# 1_Power.net
KiCad netlist of a schematic drawn in Altium Designer
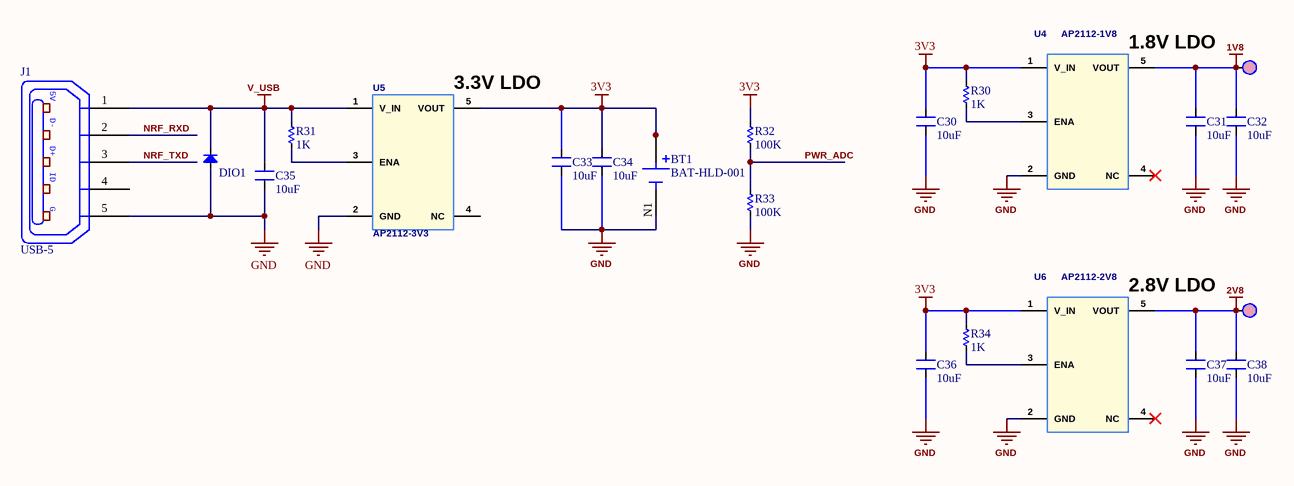
[diagram p0: [1]Power.SchDoc]

(export (version "E")
  (design (tool "Eeschema 10.0.6"))
  (components
    (comp (ref "BT1")
      (value "BAT-HLD-001")
      (footprint "BAT_BAT-HLD-001:BAT_BAT-HLD-001")
      (description "Holder for CR2032 and CR2025 Batteries, Surface-Mount, Bulk Packaging")
      (fields (field (name "MF") "Linx Technologies"))
      (libsource (lib "BAT-HLD-001") (part "BAT-HLD-001"))
    )
    (comp (ref "C30")
      (value "10uF")
      (footprint "CN-SMD-0603")
      (description "Tu gom")
      (libsource (lib "LIBTanCN") (part "CN"))
    )
    (comp (ref "C31")
      (value "10uF")
      (footprint "CN-SMD-0603")
      (description "Tu gom")
      (libsource (lib "LIBTanCN") (part "CN"))
    )
    (comp (ref "C32")
      (value "10uF")
      (footprint "CN-SMD-0603")
      (description "Tu gom")
      (libsource (lib "LIBTanCN") (part "CN"))
    )
    (comp (ref "C33")
      (value "10uF")
      (footprint "CN-SMD-0603")
      (description "Tu gom")
      (libsource (lib "LIBTanCN") (part "CN"))
    )
    (comp (ref "C34")
      (value "10uF")
      (footprint "CN-SMD-0603")
      (description "Tu gom")
      (libsource (lib "LIBTanCN") (part "CN"))
    )
    (comp (ref "C35")
      (value "10uF")
      (footprint "CN-SMD-0603")
      (description "Tu gom")
      (libsource (lib "LIBTanCN") (part "CN"))
    )
    (comp (ref "C36")
      (value "10uF")
      (footprint "CN-SMD-0603")
      (description "Tu gom")
      (libsource (lib "LIBTanCN") (part "CN"))
    )
    (comp (ref "C37")
      (value "10uF")
      (footprint "CN-SMD-0603")
      (description "Tu gom")
      (libsource (lib "LIBTanCN") (part "CN"))
    )
    (comp (ref "C38")
      (value "10uF")
      (footprint "CN-SMD-0603")
      (description "Tu gom")
      (libsource (lib "LIBTanCN") (part "CN"))
    )
    (comp (ref "DIO1")
      (value "Diode SMD")
      (footprint "DIO-SMD-123")
      (description "Default Diode")
      (fields (field (name "PUBLISHER") "Altium Limited"))
      (libsource (lib "LIBRARY") (part "Diode SMD"))
    )
    (comp (ref "J1")
      (value "USB-5")
      (footprint "USB-M1")
      (fields
        (field (name "MANUFACTURER") "FCI")
        (field (name "MANUFACTURER PART NUMBER") "10118193-0001LF")
        (field (name ".CREATOR") "MM")
        (field (name ".CHECKED PCB") "RF")
        (field (name ".CHECKED SCH") "MM")
      )
      (libsource (lib "LIBRARY") (part "USB-5"))
    )
    (comp (ref "R30")
      (value "1K")
      (footprint "RES-SMD-0603")
      (description "Resistor")
      (fields
        (field (name "MANUFACTURER") "Generic Components")
        (field (name "PUBLISHER") "Altium Hobart Technology Centre")
      )
      (libsource (lib "LIBRARY") (part "Res-SMD"))
    )
    (comp (ref "R31")
      (value "1K")
      (footprint "RES-SMD-0603")
      (description "Resistor")
      (fields
        (field (name "MANUFACTURER") "Generic Components")
        (field (name "PUBLISHER") "Altium Hobart Technology Centre")
      )
      (libsource (lib "LIBRARY") (part "Res-SMD"))
    )
    (comp (ref "R32")
      (value "100K")
      (footprint "RES-SMD-0603")
      (description "Resistor")
      (fields
        (field (name "MANUFACTURER") "Generic Components")
        (field (name "PUBLISHER") "Altium Hobart Technology Centre")
      )
      (libsource (lib "LIBRARY") (part "Res-SMD"))
    )
    (comp (ref "R33")
      (value "100K")
      (footprint "RES-SMD-0603")
      (description "Resistor")
      (fields
        (field (name "MANUFACTURER") "Generic Components")
        (field (name "PUBLISHER") "Altium Hobart Technology Centre")
      )
      (libsource (lib "LIBRARY") (part "Res-SMD"))
    )
    (comp (ref "R34")
      (value "1K")
      (footprint "RES-SMD-0603")
      (description "Resistor")
      (fields
        (field (name "MANUFACTURER") "Generic Components")
        (field (name "PUBLISHER") "Altium Hobart Technology Centre")
      )
      (libsource (lib "LIBRARY") (part "Res-SMD"))
    )
    (comp (ref "TP6")
      (value "TP")
      (footprint "P-TP 1MM")
      (libsource (lib "VitalSignal EcgPpg Board") (part "P-TESTPOINT"))
    )
    (comp (ref "TP7")
      (value "TP")
      (footprint "P-TP 1MM")
      (libsource (lib "VitalSignal EcgPpg Board") (part "P-TESTPOINT"))
    )
    (comp (ref "U4")
      (value "AP2112-1V8")
      (footprint "SOT235_AP2112")
      (description "600mA CMOS LDO REGULATOR WITH ENABLE")
      (libsource (lib "VitalSignal EcgPpg Board") (part "AP2112-1V8"))
    )
    (comp (ref "U5")
      (value "AP2112-3V3")
      (footprint "SOT235_AP2112")
      (description "600mA CMOS LDO REGULATOR WITH ENABLE")
      (libsource (lib "VitalSignal EcgPpg Board") (part "AP2112-3V3"))
    )
    (comp (ref "U6")
      (value "AP2112-2V8")
      (footprint "SOT235_AP2112")
      (description "600mA CMOS LDO REGULATOR WITH ENABLE")
      (libsource (lib "VitalSignal EcgPpg Board") (part "AP2112-1V8"))
    )
  )
  (nets
    (net (code "1") (name "/NRF_RXD") (class "Default")
      (node (ref "J1") (pin "2") (pinfunction "P2_2") (pintype "passive"))
    )
    (net (code "2") (name "/NRF_TXD") (class "Default")
      (node (ref "J1") (pin "3") (pinfunction "P3_3") (pintype "passive"))
    )
    (net (code "3") (name "/PWR_ADC") (class "Default")
      (node (ref "R32") (pin "2") (pinfunction "2_2") (pintype "passive"))
      (node (ref "R33") (pin "1") (pinfunction "1_1") (pintype "passive"))
    )
    (net (code "4") (name "1V8") (class "Default")
      (node (ref "C31") (pin "2") (pinfunction "2_2") (pintype "passive"))
      (node (ref "C32") (pin "2") (pinfunction "2_2") (pintype "passive"))
      (node (ref "TP6") (pin "1") (pinfunction "1_1") (pintype "passive"))
      (node (ref "U4") (pin "5") (pinfunction "VOUT_5") (pintype "passive"))
    )
    (net (code "5") (name "2V8") (class "Default")
      (node (ref "C37") (pin "2") (pinfunction "2_2") (pintype "passive"))
      (node (ref "C38") (pin "2") (pinfunction "2_2") (pintype "passive"))
      (node (ref "TP7") (pin "1") (pinfunction "1_1") (pintype "passive"))
      (node (ref "U6") (pin "5") (pinfunction "VOUT_5") (pintype "passive"))
    )
    (net (code "6") (name "3V3") (class "Default")
      (node (ref "BT1") (pin "P1") (pinfunction "POS_P1") (pintype "passive"))
      (node (ref "BT1") (pin "P2") (pinfunction "POS_P2") (pintype "passive"))
      (node (ref "C30") (pin "2") (pinfunction "2_2") (pintype "passive"))
      (node (ref "C33") (pin "2") (pinfunction "2_2") (pintype "passive"))
      (node (ref "C34") (pin "2") (pinfunction "2_2") (pintype "passive"))
      (node (ref "C36") (pin "2") (pinfunction "2_2") (pintype "passive"))
      (node (ref "R30") (pin "1") (pinfunction "1_1") (pintype "passive"))
      (node (ref "R32") (pin "1") (pinfunction "1_1") (pintype "passive"))
      (node (ref "R34") (pin "1") (pinfunction "1_1") (pintype "passive"))
      (node (ref "U4") (pin "1") (pinfunction "V_IN_1") (pintype "passive"))
      (node (ref "U5") (pin "5") (pinfunction "VOUT_5") (pintype "passive"))
      (node (ref "U6") (pin "1") (pinfunction "V_IN_1") (pintype "passive"))
    )
    (net (code "7") (name "GND") (class "Default")
      (node (ref "BT1") (pin "N1") (pinfunction "NEG_N1") (pintype "passive"))
      (node (ref "C30") (pin "1") (pinfunction "1_1") (pintype "passive"))
      (node (ref "C31") (pin "1") (pinfunction "1_1") (pintype "passive"))
      (node (ref "C32") (pin "1") (pinfunction "1_1") (pintype "passive"))
      (node (ref "C33") (pin "1") (pinfunction "1_1") (pintype "passive"))
      (node (ref "C34") (pin "1") (pinfunction "1_1") (pintype "passive"))
      (node (ref "C35") (pin "1") (pinfunction "1_1") (pintype "passive"))
      (node (ref "C36") (pin "1") (pinfunction "1_1") (pintype "passive"))
      (node (ref "C37") (pin "1") (pinfunction "1_1") (pintype "passive"))
      (node (ref "C38") (pin "1") (pinfunction "1_1") (pintype "passive"))
      (node (ref "DIO1") (pin "1") (pinfunction "A_1") (pintype "passive"))
      (node (ref "J1") (pin "5") (pinfunction "P5_5") (pintype "passive"))
      (node (ref "R33") (pin "2") (pinfunction "2_2") (pintype "passive"))
      (node (ref "U4") (pin "2") (pinfunction "GND_2") (pintype "passive"))
      (node (ref "U5") (pin "2") (pinfunction "GND_2") (pintype "passive"))
      (node (ref "U6") (pin "2") (pinfunction "GND_2") (pintype "passive"))
    )
    (net (code "8") (name "Net-(U4-ENA)") (class "Default")
      (node (ref "R30") (pin "2") (pinfunction "2_2") (pintype "passive"))
      (node (ref "U4") (pin "3") (pinfunction "ENA_3") (pintype "passive"))
    )
    (net (code "9") (name "Net-(U5-ENA)") (class "Default")
      (node (ref "R31") (pin "2") (pinfunction "2_2") (pintype "passive"))
      (node (ref "U5") (pin "3") (pinfunction "ENA_3") (pintype "passive"))
    )
    (net (code "10") (name "Net-(U6-ENA)") (class "Default")
      (node (ref "R34") (pin "2") (pinfunction "2_2") (pintype "passive"))
      (node (ref "U6") (pin "3") (pinfunction "ENA_3") (pintype "passive"))
    )
    (net (code "11") (name "V_USB") (class "Default")
      (node (ref "C35") (pin "2") (pinfunction "2_2") (pintype "passive"))
      (node (ref "DIO1") (pin "2") (pinfunction "K_2") (pintype "passive"))
      (node (ref "J1") (pin "1") (pinfunction "P1_1") (pintype "passive"))
      (node (ref "R31") (pin "1") (pinfunction "1_1") (pintype "passive"))
      (node (ref "U5") (pin "1") (pinfunction "V_IN_1") (pintype "passive"))
    )
    (net (code "12") (name "unconnected-(J1-P4-Pad4)") (class "Default")
      (node (ref "J1") (pin "4") (pinfunction "P4_4") (pintype "passive"))
    )
    (net (code "13") (name "unconnected-(U4-NC-Pad4)") (class "Default")
      (node (ref "U4") (pin "4") (pinfunction "NC_4") (pintype "passive+no_connect"))
    )
    (net (code "14") (name "unconnected-(U5-NC-Pad4)") (class "Default")
      (node (ref "U5") (pin "4") (pinfunction "NC_4") (pintype "passive"))
    )
    (net (code "15") (name "unconnected-(U6-NC-Pad4)") (class "Default")
      (node (ref "U6") (pin "4") (pinfunction "NC_4") (pintype "passive+no_connect"))
    )
  )
)
